# MSP_Breakout.net
KiCad netlist of a schematic drawn in EAGLE
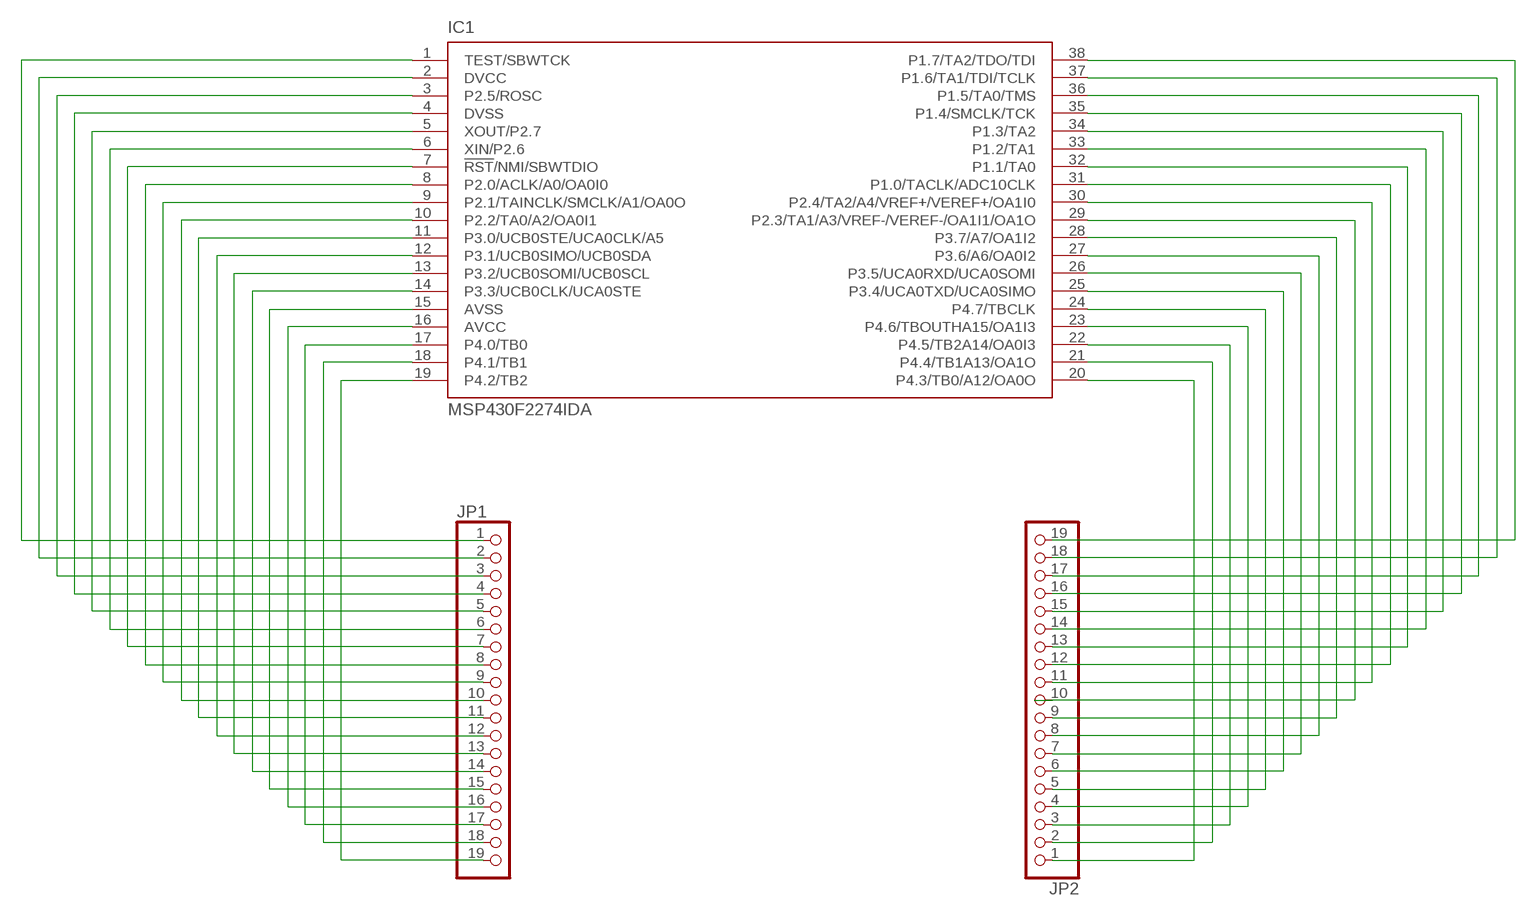
[diagram p0: schematic, sheet 1]

(export (version "E")
  (design (tool "Eeschema 10.0.6"))
  (components
    (comp (ref "IC1")
      (value "MSP430F2274IDA")
      (footprint "eagle-import:TSSOP38_R-PDSO-G38-DA")
      (libsource (lib "eagle-import") (part "MSP430F224IDA7"))
    )
    (comp (ref "JP1")
      (value "PINHD-1X19")
      (footprint "eagle-import:1X19")
      (libsource (lib "eagle-import") (part "PINHD-1X19"))
    )
    (comp (ref "JP2")
      (value "PINHD-1X19")
      (footprint "eagle-import:1X19")
      (libsource (lib "eagle-import") (part "PINHD-1X19"))
    )
  )
  (nets
    (net (code "1") (name "Net-(IC1-AVCC)") (class "Default")
      (node (ref "IC1") (pin "16") (pinfunction "AVCC_16") (pintype "power_in"))
      (node (ref "JP1") (pin "16") (pinfunction "16_16") (pintype "passive"))
    )
    (net (code "2") (name "Net-(IC1-AVSS)") (class "Default")
      (node (ref "IC1") (pin "15") (pinfunction "AVSS_15") (pintype "power_in"))
      (node (ref "JP1") (pin "15") (pinfunction "15_15") (pintype "passive"))
    )
    (net (code "3") (name "Net-(IC1-DVCC)") (class "Default")
      (node (ref "IC1") (pin "2") (pinfunction "DVCC_2") (pintype "power_in"))
      (node (ref "JP1") (pin "2") (pinfunction "2_2") (pintype "passive"))
    )
    (net (code "4") (name "Net-(IC1-DVSS)") (class "Default")
      (node (ref "IC1") (pin "4") (pinfunction "DVSS_4") (pintype "power_in"))
      (node (ref "JP1") (pin "4") (pinfunction "4_4") (pintype "passive"))
    )
    (net (code "5") (name "Net-(IC1-P1.0{slash}TACLK{slash}ADC10CLK)") (class "Default")
      (node (ref "IC1") (pin "31") (pinfunction "P1.0/TACLK/ADC10CLK_31") (pintype "bidirectional"))
      (node (ref "JP2") (pin "12") (pinfunction "12_12") (pintype "passive"))
    )
    (net (code "6") (name "Net-(IC1-P1.1{slash}TA0)") (class "Default")
      (node (ref "IC1") (pin "32") (pinfunction "P1.1/TA0_32") (pintype "bidirectional"))
      (node (ref "JP2") (pin "13") (pinfunction "13_13") (pintype "passive"))
    )
    (net (code "7") (name "Net-(IC1-P1.2{slash}TA1)") (class "Default")
      (node (ref "IC1") (pin "33") (pinfunction "P1.2/TA1_33") (pintype "bidirectional"))
      (node (ref "JP2") (pin "14") (pinfunction "14_14") (pintype "passive"))
    )
    (net (code "8") (name "Net-(IC1-P1.3{slash}TA2)") (class "Default")
      (node (ref "IC1") (pin "34") (pinfunction "P1.3/TA2_34") (pintype "bidirectional"))
      (node (ref "JP2") (pin "15") (pinfunction "15_15") (pintype "passive"))
    )
    (net (code "9") (name "Net-(IC1-P1.4{slash}SMCLK{slash}TCK)") (class "Default")
      (node (ref "IC1") (pin "35") (pinfunction "P1.4/SMCLK/TCK_35") (pintype "bidirectional"))
      (node (ref "JP2") (pin "16") (pinfunction "16_16") (pintype "passive"))
    )
    (net (code "10") (name "Net-(IC1-P1.5{slash}TA0{slash}TMS)") (class "Default")
      (node (ref "IC1") (pin "36") (pinfunction "P1.5/TA0/TMS_36") (pintype "bidirectional"))
      (node (ref "JP2") (pin "17") (pinfunction "17_17") (pintype "passive"))
    )
    (net (code "11") (name "Net-(IC1-P1.6{slash}TA1{slash}TDI{slash}TCLK)") (class "Default")
      (node (ref "IC1") (pin "37") (pinfunction "P1.6/TA1/TDI/TCLK_37") (pintype "bidirectional"))
      (node (ref "JP2") (pin "18") (pinfunction "18_18") (pintype "passive"))
    )
    (net (code "12") (name "Net-(IC1-P1.7{slash}TA2{slash}TDO{slash}TDI)") (class "Default")
      (node (ref "IC1") (pin "38") (pinfunction "P1.7/TA2/TDO/TDI_38") (pintype "bidirectional"))
      (node (ref "JP2") (pin "19") (pinfunction "19_19") (pintype "passive"))
    )
    (net (code "13") (name "Net-(IC1-P2.0{slash}ACLK{slash}A0{slash}OA0I0)") (class "Default")
      (node (ref "IC1") (pin "8") (pinfunction "P2.0/ACLK/A0/OA0I0_8") (pintype "bidirectional"))
      (node (ref "JP1") (pin "8") (pinfunction "8_8") (pintype "passive"))
    )
    (net (code "14") (name "Net-(IC1-P2.1{slash}TAINCLK{slash}SMCLK{slash}A1{slash}OA0O)") (class "Default")
      (node (ref "IC1") (pin "9") (pinfunction "P2.1/TAINCLK/SMCLK/A1/OA0O_9") (pintype "bidirectional"))
      (node (ref "JP1") (pin "9") (pinfunction "9_9") (pintype "passive"))
    )
    (net (code "15") (name "Net-(IC1-P2.2{slash}TA0{slash}A2{slash}OA0I1)") (class "Default")
      (node (ref "IC1") (pin "10") (pinfunction "P2.2/TA0/A2/OA0I1_10") (pintype "bidirectional"))
      (node (ref "JP1") (pin "10") (pinfunction "10_10") (pintype "passive"))
    )
    (net (code "16") (name "Net-(IC1-P2.3{slash}TA1{slash}A3{slash}VREF-{slash}VEREF-{slash}OA1I1{slash}OA1O)") (class "Default")
      (node (ref "IC1") (pin "29") (pinfunction "P2.3/TA1/A3/VREF-/VEREF-/OA1I1/OA1O_29") (pintype "bidirectional"))
      (node (ref "JP2") (pin "10") (pinfunction "10_10") (pintype "passive"))
    )
    (net (code "17") (name "Net-(IC1-P2.4{slash}TA2{slash}A4{slash}VREF+{slash}VEREF+{slash}OA1I0)") (class "Default")
      (node (ref "IC1") (pin "30") (pinfunction "P2.4/TA2/A4/VREF+/VEREF+/OA1I0_30") (pintype "bidirectional"))
      (node (ref "JP2") (pin "11") (pinfunction "11_11") (pintype "passive"))
    )
    (net (code "18") (name "Net-(IC1-P2.5{slash}ROSC)") (class "Default")
      (node (ref "IC1") (pin "3") (pinfunction "P2.5/ROSC_3") (pintype "bidirectional"))
      (node (ref "JP1") (pin "3") (pinfunction "3_3") (pintype "passive"))
    )
    (net (code "19") (name "Net-(IC1-P3.0{slash}UCB0STE{slash}UCA0CLK{slash}A5)") (class "Default")
      (node (ref "IC1") (pin "11") (pinfunction "P3.0/UCB0STE/UCA0CLK/A5_11") (pintype "bidirectional"))
      (node (ref "JP1") (pin "11") (pinfunction "11_11") (pintype "passive"))
    )
    (net (code "20") (name "Net-(IC1-P3.1{slash}UCB0SIMO{slash}UCB0SDA)") (class "Default")
      (node (ref "IC1") (pin "12") (pinfunction "P3.1/UCB0SIMO/UCB0SDA_12") (pintype "bidirectional"))
      (node (ref "JP1") (pin "12") (pinfunction "12_12") (pintype "passive"))
    )
    (net (code "21") (name "Net-(IC1-P3.2{slash}UCB0SOMI{slash}UCB0SCL)") (class "Default")
      (node (ref "IC1") (pin "13") (pinfunction "P3.2/UCB0SOMI/UCB0SCL_13") (pintype "bidirectional"))
      (node (ref "JP1") (pin "13") (pinfunction "13_13") (pintype "passive"))
    )
    (net (code "22") (name "Net-(IC1-P3.3{slash}UCB0CLK{slash}UCA0STE)") (class "Default")
      (node (ref "IC1") (pin "14") (pinfunction "P3.3/UCB0CLK/UCA0STE_14") (pintype "bidirectional"))
      (node (ref "JP1") (pin "14") (pinfunction "14_14") (pintype "passive"))
    )
    (net (code "23") (name "Net-(IC1-P3.4{slash}UCA0TXD{slash}UCA0SIMO)") (class "Default")
      (node (ref "IC1") (pin "25") (pinfunction "P3.4/UCA0TXD/UCA0SIMO_25") (pintype "bidirectional"))
      (node (ref "JP2") (pin "6") (pinfunction "6_6") (pintype "passive"))
    )
    (net (code "24") (name "Net-(IC1-P3.5{slash}UCA0RXD{slash}UCA0SOMI)") (class "Default")
      (node (ref "IC1") (pin "26") (pinfunction "P3.5/UCA0RXD/UCA0SOMI_26") (pintype "bidirectional"))
      (node (ref "JP2") (pin "7") (pinfunction "7_7") (pintype "passive"))
    )
    (net (code "25") (name "Net-(IC1-P3.6{slash}A6{slash}OA0I2)") (class "Default")
      (node (ref "IC1") (pin "27") (pinfunction "P3.6/A6/OA0I2_27") (pintype "bidirectional"))
      (node (ref "JP2") (pin "8") (pinfunction "8_8") (pintype "passive"))
    )
    (net (code "26") (name "Net-(IC1-P3.7{slash}A7{slash}OA1I2)") (class "Default")
      (node (ref "IC1") (pin "28") (pinfunction "P3.7/A7/OA1I2_28") (pintype "bidirectional"))
      (node (ref "JP2") (pin "9") (pinfunction "9_9") (pintype "passive"))
    )
    (net (code "27") (name "Net-(IC1-P4.0{slash}TB0)") (class "Default")
      (node (ref "IC1") (pin "17") (pinfunction "P4.0/TB0_17") (pintype "bidirectional"))
      (node (ref "JP1") (pin "17") (pinfunction "17_17") (pintype "passive"))
    )
    (net (code "28") (name "Net-(IC1-P4.1{slash}TB1)") (class "Default")
      (node (ref "IC1") (pin "18") (pinfunction "P4.1/TB1_18") (pintype "bidirectional"))
      (node (ref "JP1") (pin "18") (pinfunction "18_18") (pintype "passive"))
    )
    (net (code "29") (name "Net-(IC1-P4.2{slash}TB2)") (class "Default")
      (node (ref "IC1") (pin "19") (pinfunction "P4.2/TB2_19") (pintype "bidirectional"))
      (node (ref "JP1") (pin "19") (pinfunction "19_19") (pintype "passive"))
    )
    (net (code "30") (name "Net-(IC1-P4.3{slash}TB0{slash}A12{slash}OA0O)") (class "Default")
      (node (ref "IC1") (pin "20") (pinfunction "P4.3/TB0/A12/OA0O_20") (pintype "bidirectional"))
      (node (ref "JP2") (pin "1") (pinfunction "1_1") (pintype "passive"))
    )
    (net (code "31") (name "Net-(IC1-P4.4{slash}TB1A13{slash}OA1O)") (class "Default")
      (node (ref "IC1") (pin "21") (pinfunction "P4.4/TB1A13/OA1O_21") (pintype "bidirectional"))
      (node (ref "JP2") (pin "2") (pinfunction "2_2") (pintype "passive"))
    )
    (net (code "32") (name "Net-(IC1-P4.5{slash}TB2A14{slash}OA0I3)") (class "Default")
      (node (ref "IC1") (pin "22") (pinfunction "P4.5/TB2A14/OA0I3_22") (pintype "bidirectional"))
      (node (ref "JP2") (pin "3") (pinfunction "3_3") (pintype "passive"))
    )
    (net (code "33") (name "Net-(IC1-P4.6{slash}TBOUTHA15{slash}OA1I3)") (class "Default")
      (node (ref "IC1") (pin "23") (pinfunction "P4.6/TBOUTHA15/OA1I3_23") (pintype "bidirectional"))
      (node (ref "JP2") (pin "4") (pinfunction "4_4") (pintype "passive"))
    )
    (net (code "34") (name "Net-(IC1-P4.7{slash}TBCLK)") (class "Default")
      (node (ref "IC1") (pin "24") (pinfunction "P4.7/TBCLK_24") (pintype "bidirectional"))
      (node (ref "JP2") (pin "5") (pinfunction "5_5") (pintype "passive"))
    )
    (net (code "35") (name "Net-(IC1-TEST{slash}SBWTCK)") (class "Default")
      (node (ref "IC1") (pin "1") (pinfunction "TEST/SBWTCK_1") (pintype "input"))
      (node (ref "JP1") (pin "1") (pinfunction "1_1") (pintype "passive"))
    )
    (net (code "36") (name "Net-(IC1-XIN{slash}P2.6)") (class "Default")
      (node (ref "IC1") (pin "6") (pinfunction "XIN/P2.6_6") (pintype "bidirectional"))
      (node (ref "JP1") (pin "6") (pinfunction "6_6") (pintype "passive"))
    )
    (net (code "37") (name "Net-(IC1-XOUT{slash}P2.7)") (class "Default")
      (node (ref "IC1") (pin "5") (pinfunction "XOUT/P2.7_5") (pintype "bidirectional"))
      (node (ref "JP1") (pin "5") (pinfunction "5_5") (pintype "passive"))
    )
    (net (code "38") (name "Net-(IC1-~{RST}{slash}NMI{slash}SBWTDIO)") (class "Default")
      (node (ref "IC1") (pin "7") (pinfunction "~{RST}/NMI/SBWTDIO_7") (pintype "input"))
      (node (ref "JP1") (pin "7") (pinfunction "7_7") (pintype "passive"))
    )
  )
)
